# esp07_1w.net
KiCad netlist of a schematic drawn in EAGLE
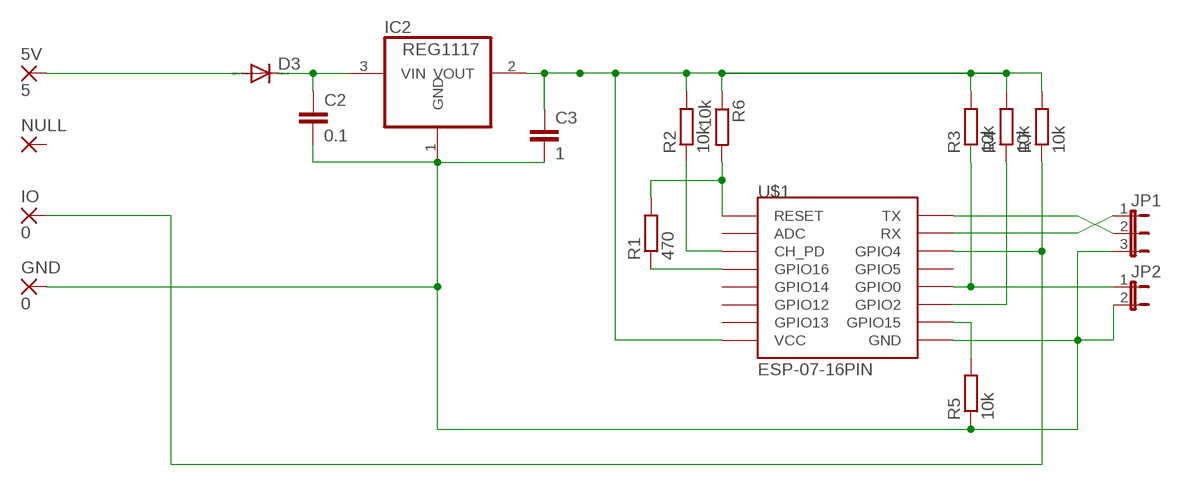
[diagram p0: schematic, sheet 1]

(export (version "E")
  (design (tool "Eeschema 10.0.6"))
  (components
    (comp (ref "5V")
      (value "5")
      (footprint "eagle-import:3,81_1,4")
      (libsource (lib "eagle-import") (part "3,81/1,4"))
    )
    (comp (ref "C2")
      (value "0.1")
      (footprint "eagle-import:C0805")
      (libsource (lib "eagle-import") (part "C-EUC0805"))
    )
    (comp (ref "C3")
      (value "1")
      (footprint "eagle-import:C0805")
      (libsource (lib "eagle-import") (part "C-EUC0805"))
    )
    (comp (ref "D3")
      (value "DIODE-SOD80C")
      (footprint "eagle-import:SOD80C")
      (libsource (lib "eagle-import") (part "DIODE-SOD80C"))
    )
    (comp (ref "GND")
      (value "0")
      (footprint "eagle-import:3,81_1,4")
      (libsource (lib "eagle-import") (part "3,81/1,4"))
    )
    (comp (ref "IC2")
      (value "REG1117")
      (footprint "eagle-import:SOT223")
      (libsource (lib "eagle-import") (part "REG1117"))
    )
    (comp (ref "IO")
      (value "0")
      (footprint "eagle-import:3,81_1,4")
      (libsource (lib "eagle-import") (part "3,81/1,4"))
    )
    (comp (ref "JP1")
      (value "JP2E")
      (footprint "eagle-import:JP2")
      (libsource (lib "eagle-import") (part "JP2E"))
    )
    (comp (ref "JP2")
      (value "JP1E")
      (footprint "eagle-import:JP1")
      (libsource (lib "eagle-import") (part "JP1E"))
    )
    (comp (ref "NULL")
      (value "3,81/1,4")
      (footprint "eagle-import:3,81_1,4")
      (libsource (lib "eagle-import") (part "3,81/1,4"))
    )
    (comp (ref "R1")
      (value "470")
      (footprint "eagle-import:R1206")
      (libsource (lib "eagle-import") (part "R-EU_R1206"))
    )
    (comp (ref "R2")
      (value "10k")
      (footprint "eagle-import:R1206")
      (libsource (lib "eagle-import") (part "R-EU_R1206"))
    )
    (comp (ref "R3")
      (value "10k")
      (footprint "eagle-import:R1206")
      (libsource (lib "eagle-import") (part "R-EU_R1206"))
    )
    (comp (ref "R4")
      (value "10k")
      (footprint "eagle-import:R1206")
      (libsource (lib "eagle-import") (part "R-EU_R1206"))
    )
    (comp (ref "R5")
      (value "10k")
      (footprint "eagle-import:R1206")
      (libsource (lib "eagle-import") (part "R-EU_R1206"))
    )
    (comp (ref "R6")
      (value "10k")
      (footprint "eagle-import:R1206")
      (libsource (lib "eagle-import") (part "R-EU_R1206"))
    )
    (comp (ref "R7")
      (value "10k")
      (footprint "eagle-import:R1206")
      (libsource (lib "eagle-import") (part "R-EU_R1206"))
    )
    (comp (ref "U$1")
      (value "ESP-07-16PIN")
      (footprint "eagle-import:ESP-07-16PIN")
      (libsource (lib "eagle-import") (part "ESP-07-16PIN"))
    )
  )
  (nets
    (net (code "1") (name "Net-(5V-P)") (class "Default")
      (node (ref "5V") (pin "1") (pinfunction "P_1") (pintype "passive"))
      (node (ref "D3") (pin "A") (pinfunction "A_A") (pintype "passive"))
    )
    (net (code "2") (name "Net-(GND-P)") (class "Default")
      (node (ref "C2") (pin "2") (pinfunction "2_2") (pintype "passive"))
      (node (ref "C3") (pin "2") (pinfunction "2_2") (pintype "passive"))
      (node (ref "GND") (pin "1") (pinfunction "P_1") (pintype "passive"))
      (node (ref "IC2") (pin "1") (pinfunction "GND_1") (pintype "power_in"))
      (node (ref "JP1") (pin "3") (pinfunction "3_3") (pintype "passive"))
      (node (ref "JP2") (pin "2") (pinfunction "2_2") (pintype "passive"))
      (node (ref "R5") (pin "1") (pinfunction "1_1") (pintype "passive"))
      (node (ref "U$1") (pin "GND") (pinfunction "GND_GND") (pintype "bidirectional"))
    )
    (net (code "3") (name "Net-(IC2-VIN)") (class "Default")
      (node (ref "C2") (pin "1") (pinfunction "1_1") (pintype "passive"))
      (node (ref "D3") (pin "C") (pinfunction "C_C") (pintype "passive"))
      (node (ref "IC2") (pin "3") (pinfunction "VIN_3") (pintype "input"))
    )
    (net (code "4") (name "Net-(IC2-VOUT)") (class "Default")
      (node (ref "C3") (pin "1") (pinfunction "1_1") (pintype "passive"))
      (node (ref "IC2") (pin "2") (pinfunction "VOUT_2") (pintype "output"))
      (node (ref "R2") (pin "2") (pinfunction "2_2") (pintype "passive"))
      (node (ref "R3") (pin "2") (pinfunction "2_2") (pintype "passive"))
      (node (ref "R4") (pin "2") (pinfunction "2_2") (pintype "passive"))
      (node (ref "R6") (pin "1") (pinfunction "1_1") (pintype "passive"))
      (node (ref "R7") (pin "2") (pinfunction "2_2") (pintype "passive"))
      (node (ref "U$1") (pin "VCC") (pinfunction "VCC_VCC") (pintype "bidirectional"))
    )
    (net (code "5") (name "Net-(IO-P)") (class "Default")
      (node (ref "IO") (pin "1") (pinfunction "P_1") (pintype "passive"))
      (node (ref "R7") (pin "1") (pinfunction "1_1") (pintype "passive"))
      (node (ref "U$1") (pin "GPIO4") (pinfunction "GPIO4_GPIO4") (pintype "bidirectional"))
    )
    (net (code "6") (name "Net-(JP1-Pad1)") (class "Default")
      (node (ref "JP1") (pin "1") (pinfunction "1_1") (pintype "passive"))
      (node (ref "U$1") (pin "RX") (pinfunction "RX_RX") (pintype "bidirectional"))
    )
    (net (code "7") (name "Net-(JP1-Pad2)") (class "Default")
      (node (ref "JP1") (pin "2") (pinfunction "2_2") (pintype "passive"))
      (node (ref "U$1") (pin "TX") (pinfunction "TX_TX") (pintype "bidirectional"))
    )
    (net (code "8") (name "Net-(JP2-Pad1)") (class "Default")
      (node (ref "JP2") (pin "1") (pinfunction "1_1") (pintype "passive"))
      (node (ref "R3") (pin "1") (pinfunction "1_1") (pintype "passive"))
      (node (ref "U$1") (pin "GPIO0") (pinfunction "GPIO0_GPIO0") (pintype "bidirectional"))
    )
    (net (code "9") (name "Net-(R1-Pad1)") (class "Default")
      (node (ref "R1") (pin "1") (pinfunction "1_1") (pintype "passive"))
      (node (ref "U$1") (pin "GPIO16") (pinfunction "GPIO16_GPIO16") (pintype "bidirectional"))
    )
    (net (code "10") (name "Net-(R2-Pad1)") (class "Default")
      (node (ref "R2") (pin "1") (pinfunction "1_1") (pintype "passive"))
      (node (ref "U$1") (pin "CH_PD") (pinfunction "CH_PD_CH_PD") (pintype "bidirectional"))
    )
    (net (code "11") (name "Net-(R4-Pad1)") (class "Default")
      (node (ref "R4") (pin "1") (pinfunction "1_1") (pintype "passive"))
      (node (ref "U$1") (pin "GPIO2") (pinfunction "GPIO2_GPIO2") (pintype "bidirectional"))
    )
    (net (code "12") (name "Net-(R5-Pad2)") (class "Default")
      (node (ref "R5") (pin "2") (pinfunction "2_2") (pintype "passive"))
      (node (ref "U$1") (pin "GPIO15") (pinfunction "GPIO15_GPIO15") (pintype "bidirectional"))
    )
    (net (code "13") (name "Net-(U$1-RESET)") (class "Default")
      (node (ref "R1") (pin "2") (pinfunction "2_2") (pintype "passive"))
      (node (ref "R6") (pin "2") (pinfunction "2_2") (pintype "passive"))
      (node (ref "U$1") (pin "REST") (pinfunction "RESET_REST") (pintype "bidirectional"))
    )
    (net (code "14") (name "unconnected-(NULL-P-Pad1)") (class "Default")
      (node (ref "NULL") (pin "1") (pinfunction "P_1") (pintype "passive"))
    )
    (net (code "15") (name "unconnected-(U$1-PadADC)") (class "Default")
      (node (ref "U$1") (pin "ADC") (pinfunction "ADC_ADC") (pintype "bidirectional"))
    )
    (net (code "16") (name "unconnected-(U$1-PadGPIO5)") (class "Default")
      (node (ref "U$1") (pin "GPIO5") (pinfunction "GPIO5_GPIO5") (pintype "bidirectional"))
    )
    (net (code "17") (name "unconnected-(U$1-PadGPIO12)") (class "Default")
      (node (ref "U$1") (pin "GPIO12") (pinfunction "GPIO12_GPIO12") (pintype "bidirectional"))
    )
    (net (code "18") (name "unconnected-(U$1-PadGPIO13)") (class "Default")
      (node (ref "U$1") (pin "GPIO13") (pinfunction "GPIO13_GPIO13") (pintype "bidirectional"))
    )
    (net (code "19") (name "unconnected-(U$1-PadGPIO14)") (class "Default")
      (node (ref "U$1") (pin "GPIO14") (pinfunction "GPIO14_GPIO14") (pintype "bidirectional"))
    )
  )
)
